# CAN-D_Coat_Rev2.net
KiCad netlist of a schematic drawn in EAGLE
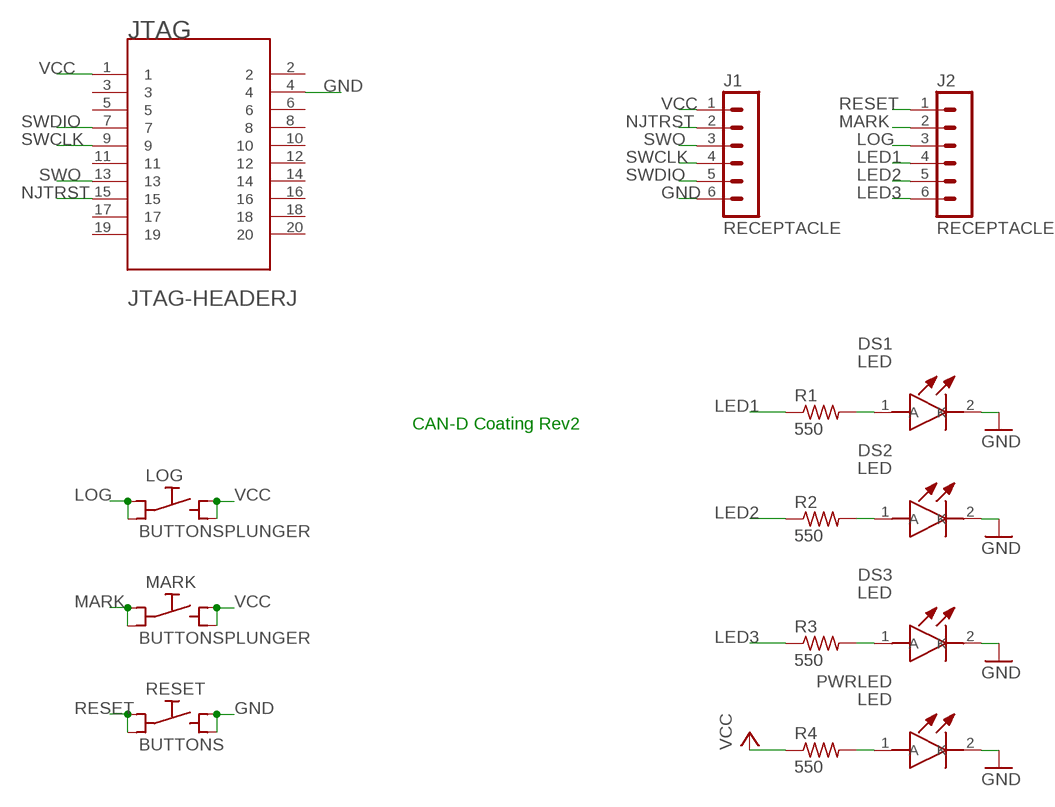
[diagram p0: schematic, sheet 1]

(export (version "E")
  (design (tool "Eeschema 10.0.6"))
  (components
    (comp (ref "DS1")
      (value "LED")
      (footprint "eagle-import:L130-6580001400001")
      (fields
        (field (name "MANUFACTURER_PART_NUMBER") "L130-6580001400001")
        (field (name "MOUSER_PART_NUMBER") "997-L130-65800014001")
        (field (name "RS_PART_NUMBER") "1709867")
      )
      (libsource (lib "eagle-import") (part "LED"))
    )
    (comp (ref "DS2")
      (value "LED")
      (footprint "eagle-import:L130-6580001400001")
      (fields
        (field (name "MANUFACTURER_PART_NUMBER") "L130-6580001400001")
        (field (name "MOUSER_PART_NUMBER") "997-L130-65800014001")
        (field (name "RS_PART_NUMBER") "1709867")
      )
      (libsource (lib "eagle-import") (part "LED"))
    )
    (comp (ref "DS3")
      (value "LED")
      (footprint "eagle-import:L130-6580001400001")
      (fields
        (field (name "MANUFACTURER_PART_NUMBER") "L130-6580001400001")
        (field (name "MOUSER_PART_NUMBER") "997-L130-65800014001")
        (field (name "RS_PART_NUMBER") "1709867")
      )
      (libsource (lib "eagle-import") (part "LED"))
    )
    (comp (ref "J1")
      (value "RECEPTACLE")
      (footprint "eagle-import:SSM-106-L-SV-K-TR")
      (libsource (lib "eagle-import") (part "RECEPTACLE"))
    )
    (comp (ref "J2")
      (value "RECEPTACLE")
      (footprint "eagle-import:SSM-106-L-SV-K-TR")
      (libsource (lib "eagle-import") (part "RECEPTACLE"))
    )
    (comp (ref "JTAG")
      (value "JTAG-HEADERJ")
      (footprint "eagle-import:TSM-110-02-S-DV-P-TR")
      (fields
        (field (name "DIGI-KEY_PART_NUMBER") "SAM14887CT-ND")
        (field (name "MF") "Samtec Inc.")
        (field (name "MP") "TSM-110-01-T-DV-TR")
      )
      (libsource (lib "eagle-import") (part "JTAG-HEADERJ"))
    )
    (comp (ref "LOG")
      (value "BUTTONSPLUNGER")
      (footprint "eagle-import:TL3301SPF260QG")
      (libsource (lib "eagle-import") (part "BUTTONSPLUNGER"))
    )
    (comp (ref "MARK")
      (value "BUTTONSPLUNGER")
      (footprint "eagle-import:TL3301SPF260QG")
      (libsource (lib "eagle-import") (part "BUTTONSPLUNGER"))
    )
    (comp (ref "PWRLED")
      (value "LED")
      (footprint "eagle-import:L130-6580001400001")
      (fields
        (field (name "MANUFACTURER_PART_NUMBER") "L130-6580001400001")
        (field (name "MOUSER_PART_NUMBER") "997-L130-65800014001")
        (field (name "RS_PART_NUMBER") "1709867")
      )
      (libsource (lib "eagle-import") (part "LED"))
    )
    (comp (ref "R1")
      (value "550")
      (footprint "eagle-import:R0603")
      (libsource (lib "eagle-import") (part "RESISTOR"))
    )
    (comp (ref "R2")
      (value "550")
      (footprint "eagle-import:R0603")
      (libsource (lib "eagle-import") (part "RESISTOR"))
    )
    (comp (ref "R3")
      (value "550")
      (footprint "eagle-import:R0603")
      (libsource (lib "eagle-import") (part "R-US_R0603"))
    )
    (comp (ref "R4")
      (value "550")
      (footprint "eagle-import:R0603")
      (libsource (lib "eagle-import") (part "RESISTOR"))
    )
    (comp (ref "RESET")
      (value "BUTTONS")
      (footprint "eagle-import:1301.9314")
      (libsource (lib "eagle-import") (part "BUTTONS"))
    )
  )
  (nets
    (net (code "1") (name "/LED1") (class "Default")
      (node (ref "J2") (pin "4") (pinfunction "4_4") (pintype "passive"))
      (node (ref "R1") (pin "1") (pinfunction "1_1") (pintype "passive"))
    )
    (net (code "2") (name "/LED2") (class "Default")
      (node (ref "J2") (pin "5") (pinfunction "5_5") (pintype "passive"))
      (node (ref "R2") (pin "1") (pinfunction "1_1") (pintype "passive"))
    )
    (net (code "3") (name "/LED3") (class "Default")
      (node (ref "J2") (pin "6") (pinfunction "6_6") (pintype "passive"))
      (node (ref "R3") (pin "1") (pinfunction "1_1") (pintype "passive"))
    )
    (net (code "4") (name "/LOG") (class "Default")
      (node (ref "J2") (pin "3") (pinfunction "3_3") (pintype "passive"))
      (node (ref "LOG") (pin "C1") (pinfunction "C_C1") (pintype "passive"))
      (node (ref "LOG") (pin "C2") (pinfunction "C_C2") (pintype "passive"))
    )
    (net (code "5") (name "/MARK") (class "Default")
      (node (ref "J2") (pin "2") (pinfunction "2_2") (pintype "passive"))
      (node (ref "MARK") (pin "C1") (pinfunction "C_C1") (pintype "passive"))
      (node (ref "MARK") (pin "C2") (pinfunction "C_C2") (pintype "passive"))
    )
    (net (code "6") (name "/NJTRST") (class "Default")
      (node (ref "J1") (pin "2") (pinfunction "2_2") (pintype "passive"))
      (node (ref "JTAG") (pin "15") (pinfunction "15_15") (pintype "passive"))
    )
    (net (code "7") (name "/RESET") (class "Default")
      (node (ref "J2") (pin "1") (pinfunction "1_1") (pintype "passive"))
      (node (ref "RESET") (pin "C1") (pinfunction "C_C1") (pintype "passive"))
      (node (ref "RESET") (pin "C2") (pinfunction "C_C2") (pintype "passive"))
    )
    (net (code "8") (name "/SWCLK") (class "Default")
      (node (ref "J1") (pin "4") (pinfunction "4_4") (pintype "passive"))
      (node (ref "JTAG") (pin "9") (pinfunction "9_9") (pintype "passive"))
    )
    (net (code "9") (name "/SWDIO") (class "Default")
      (node (ref "J1") (pin "5") (pinfunction "5_5") (pintype "passive"))
      (node (ref "JTAG") (pin "7") (pinfunction "7_7") (pintype "passive"))
    )
    (net (code "10") (name "/SWO") (class "Default")
      (node (ref "J1") (pin "3") (pinfunction "3_3") (pintype "passive"))
      (node (ref "JTAG") (pin "13") (pinfunction "13_13") (pintype "passive"))
    )
    (net (code "11") (name "GND") (class "Default")
      (node (ref "DS1") (pin "2") (pinfunction "K_2") (pintype "bidirectional"))
      (node (ref "DS2") (pin "2") (pinfunction "K_2") (pintype "bidirectional"))
      (node (ref "DS3") (pin "2") (pinfunction "K_2") (pintype "bidirectional"))
      (node (ref "J1") (pin "6") (pinfunction "6_6") (pintype "passive"))
      (node (ref "JTAG") (pin "4") (pinfunction "4_4") (pintype "passive"))
      (node (ref "PWRLED") (pin "2") (pinfunction "K_2") (pintype "bidirectional"))
      (node (ref "RESET") (pin "NO1") (pinfunction "NO_NO1") (pintype "passive"))
      (node (ref "RESET") (pin "NO2") (pinfunction "NO_NO2") (pintype "passive"))
    )
    (net (code "12") (name "Net-(DS1-A)") (class "Default")
      (node (ref "DS1") (pin "1") (pinfunction "A_1") (pintype "bidirectional"))
      (node (ref "R1") (pin "2") (pinfunction "2_2") (pintype "passive"))
    )
    (net (code "13") (name "Net-(DS2-A)") (class "Default")
      (node (ref "DS2") (pin "1") (pinfunction "A_1") (pintype "bidirectional"))
      (node (ref "R2") (pin "2") (pinfunction "2_2") (pintype "passive"))
    )
    (net (code "14") (name "Net-(DS3-A)") (class "Default")
      (node (ref "DS3") (pin "1") (pinfunction "A_1") (pintype "bidirectional"))
      (node (ref "R3") (pin "2") (pinfunction "2_2") (pintype "passive"))
    )
    (net (code "15") (name "Net-(PWRLED-A)") (class "Default")
      (node (ref "PWRLED") (pin "1") (pinfunction "A_1") (pintype "bidirectional"))
      (node (ref "R4") (pin "2") (pinfunction "2_2") (pintype "passive"))
    )
    (net (code "16") (name "VCC") (class "Default")
      (node (ref "J1") (pin "1") (pinfunction "1_1") (pintype "passive"))
      (node (ref "JTAG") (pin "1") (pinfunction "1_1") (pintype "passive"))
      (node (ref "LOG") (pin "NO1") (pinfunction "NO_NO1") (pintype "passive"))
      (node (ref "LOG") (pin "NO2") (pinfunction "NO_NO2") (pintype "passive"))
      (node (ref "MARK") (pin "NO1") (pinfunction "NO_NO1") (pintype "passive"))
      (node (ref "MARK") (pin "NO2") (pinfunction "NO_NO2") (pintype "passive"))
      (node (ref "R4") (pin "1") (pinfunction "1_1") (pintype "passive"))
    )
    (net (code "17") (name "unconnected-(JTAG-Pad2)") (class "Default")
      (node (ref "JTAG") (pin "2") (pinfunction "2_2") (pintype "passive"))
    )
    (net (code "18") (name "unconnected-(JTAG-Pad3)") (class "Default")
      (node (ref "JTAG") (pin "3") (pinfunction "3_3") (pintype "passive"))
    )
    (net (code "19") (name "unconnected-(JTAG-Pad5)") (class "Default")
      (node (ref "JTAG") (pin "5") (pinfunction "5_5") (pintype "passive"))
    )
    (net (code "20") (name "unconnected-(JTAG-Pad6)") (class "Default")
      (node (ref "JTAG") (pin "6") (pinfunction "6_6") (pintype "passive"))
    )
    (net (code "21") (name "unconnected-(JTAG-Pad8)") (class "Default")
      (node (ref "JTAG") (pin "8") (pinfunction "8_8") (pintype "passive"))
    )
    (net (code "22") (name "unconnected-(JTAG-Pad10)") (class "Default")
      (node (ref "JTAG") (pin "10") (pinfunction "10_10") (pintype "passive"))
    )
    (net (code "23") (name "unconnected-(JTAG-Pad11)") (class "Default")
      (node (ref "JTAG") (pin "11") (pinfunction "11_11") (pintype "passive"))
    )
    (net (code "24") (name "unconnected-(JTAG-Pad12)") (class "Default")
      (node (ref "JTAG") (pin "12") (pinfunction "12_12") (pintype "passive"))
    )
    (net (code "25") (name "unconnected-(JTAG-Pad14)") (class "Default")
      (node (ref "JTAG") (pin "14") (pinfunction "14_14") (pintype "passive"))
    )
    (net (code "26") (name "unconnected-(JTAG-Pad16)") (class "Default")
      (node (ref "JTAG") (pin "16") (pinfunction "16_16") (pintype "passive"))
    )
    (net (code "27") (name "unconnected-(JTAG-Pad17)") (class "Default")
      (node (ref "JTAG") (pin "17") (pinfunction "17_17") (pintype "passive"))
    )
    (net (code "28") (name "unconnected-(JTAG-Pad18)") (class "Default")
      (node (ref "JTAG") (pin "18") (pinfunction "18_18") (pintype "passive"))
    )
    (net (code "29") (name "unconnected-(JTAG-Pad19)") (class "Default")
      (node (ref "JTAG") (pin "19") (pinfunction "19_19") (pintype "passive"))
    )
    (net (code "30") (name "unconnected-(JTAG-Pad20)") (class "Default")
      (node (ref "JTAG") (pin "20") (pinfunction "20_20") (pintype "passive"))
    )
  )
)
